# spion.net
KiCad netlist of a schematic drawn in EAGLE
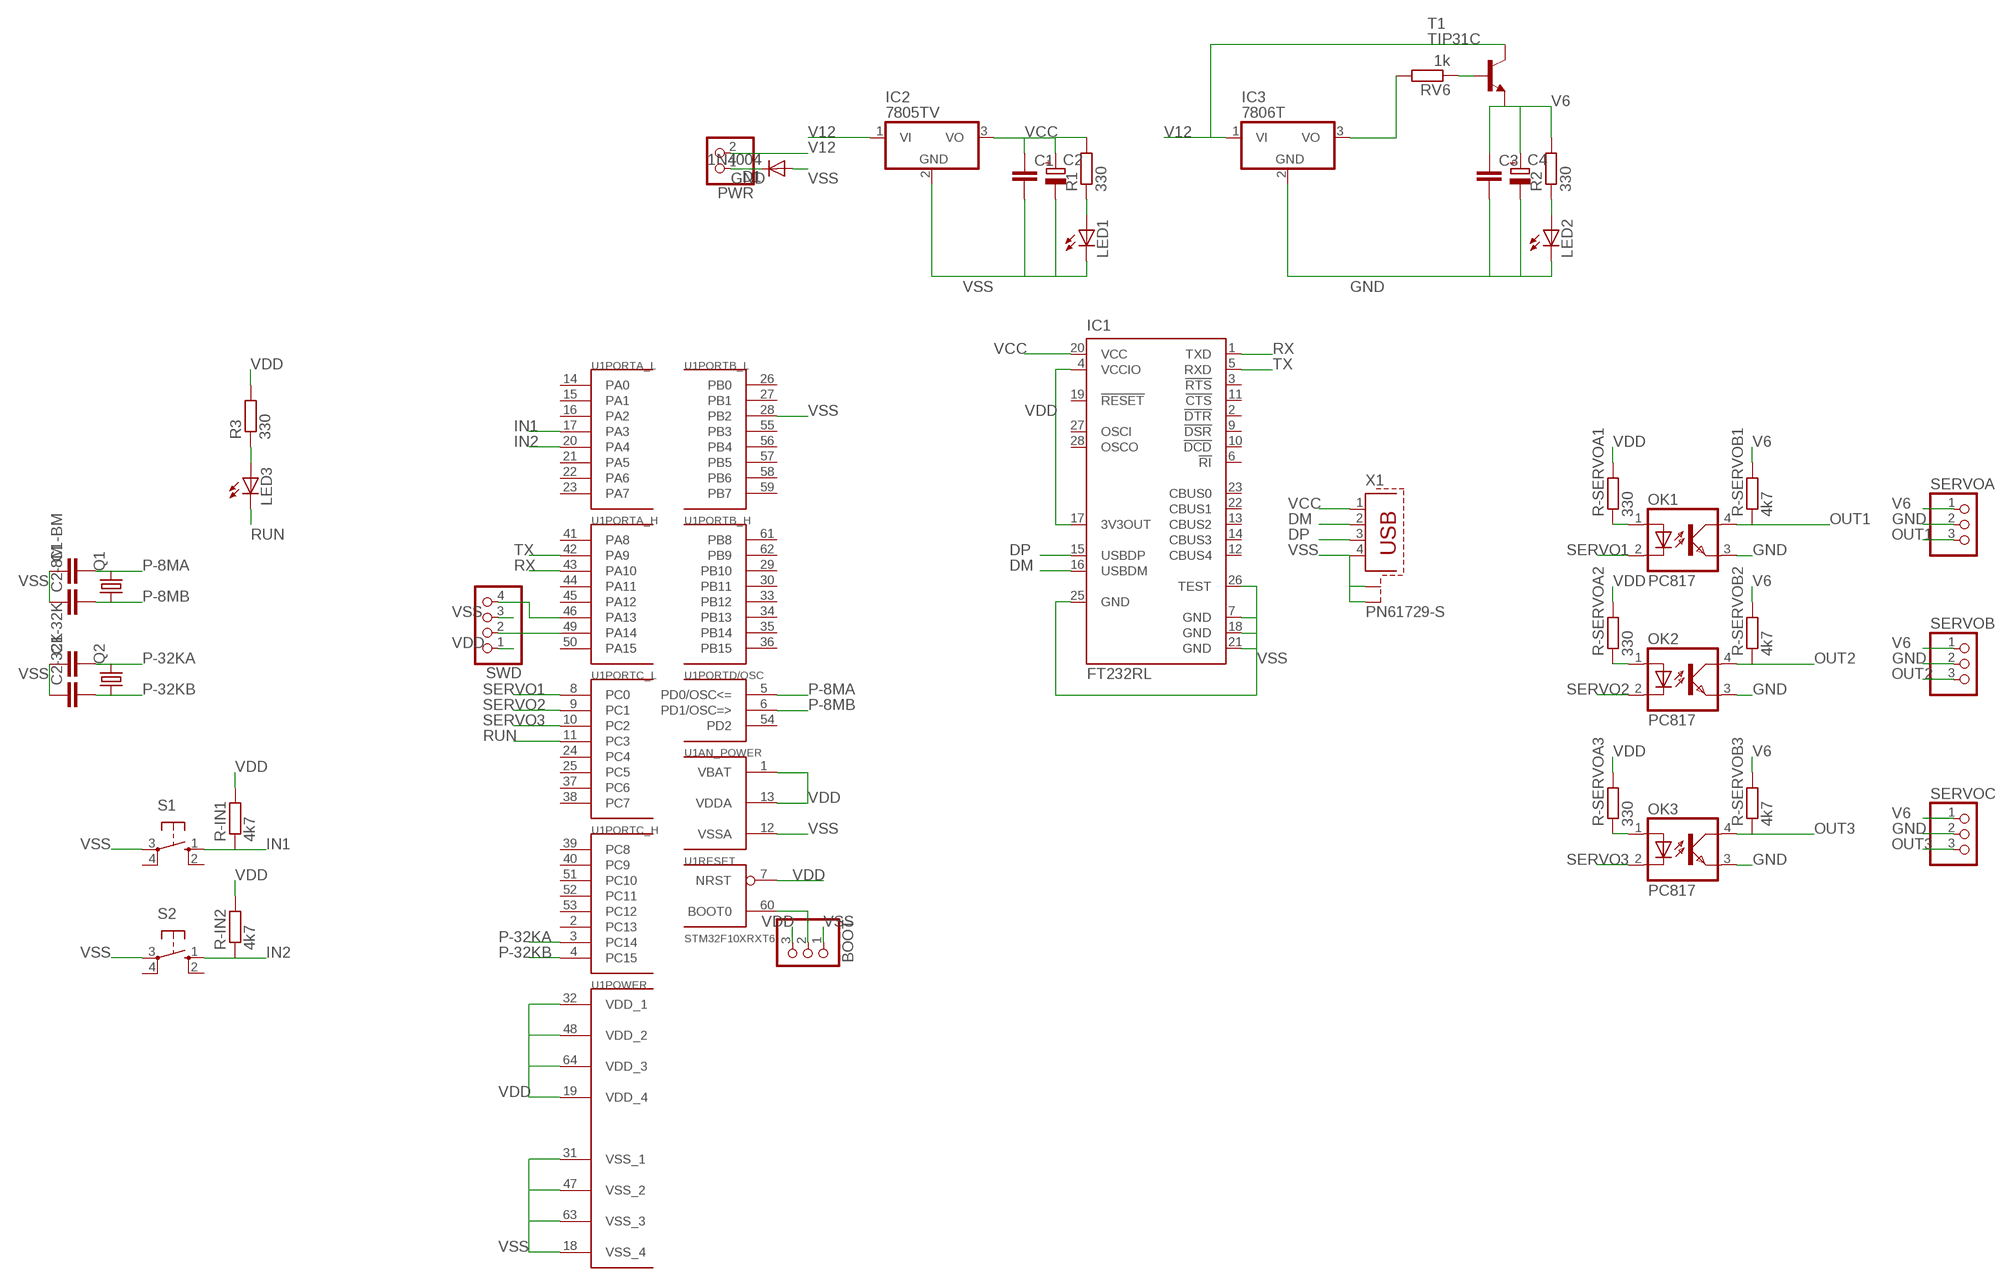
[diagram p0: schematic, sheet 1]

(export (version "E")
  (design (tool "Eeschema 10.0.6"))
  (components
    (comp (ref "BOOT")
      (value "PINHD-1X3")
      (footprint "eagle-import:1X03")
      (libsource (lib "eagle-import") (part "PINHD-1X3"))
    )
    (comp (ref "C1")
      (value "C-EU025-024X044")
      (footprint "eagle-import:C025-024X044")
      (libsource (lib "eagle-import") (part "C-EU025-024X044"))
    )
    (comp (ref "C1-32K")
      (value "C-EU025-024X044")
      (footprint "eagle-import:C025-024X044")
      (libsource (lib "eagle-import") (part "C-EU025-024X044"))
    )
    (comp (ref "C1-BM")
      (value "C-EU025-024X044")
      (footprint "eagle-import:C025-024X044")
      (libsource (lib "eagle-import") (part "C-EU025-024X044"))
    )
    (comp (ref "C2")
      (value "CPOL-EUE2-5")
      (footprint "eagle-import:E2-5")
      (libsource (lib "eagle-import") (part "CPOL-EUE2-5"))
    )
    (comp (ref "C2-8M")
      (value "C-EU025-024X044")
      (footprint "eagle-import:C025-024X044")
      (libsource (lib "eagle-import") (part "C-EU025-024X044"))
    )
    (comp (ref "C2-32K")
      (value "C-EU025-024X044")
      (footprint "eagle-import:C025-024X044")
      (libsource (lib "eagle-import") (part "C-EU025-024X044"))
    )
    (comp (ref "C3")
      (value "C-EU025-024X044")
      (footprint "eagle-import:C025-024X044")
      (libsource (lib "eagle-import") (part "C-EU025-024X044"))
    )
    (comp (ref "C4")
      (value "CPOL-EUE2-5")
      (footprint "eagle-import:E2-5")
      (libsource (lib "eagle-import") (part "CPOL-EUE2-5"))
    )
    (comp (ref "D1")
      (value "1N4004")
      (footprint "eagle-import:DO41-10")
      (libsource (lib "eagle-import") (part "1N4004"))
    )
    (comp (ref "IC1")
      (value "FT232RL")
      (footprint "eagle-import:SSOP28")
      (libsource (lib "eagle-import") (part "FT232RL"))
    )
    (comp (ref "IC2")
      (value "7805TV")
      (footprint "eagle-import:TO220V")
      (libsource (lib "eagle-import") (part "78TV05"))
    )
    (comp (ref "IC3")
      (value "7806T")
      (footprint "eagle-import:TO220H")
      (libsource (lib "eagle-import") (part "78T06"))
    )
    (comp (ref "LED1")
      (value "LED3MM")
      (footprint "eagle-import:LED3MM")
      (libsource (lib "eagle-import") (part "LED3MM"))
    )
    (comp (ref "LED2")
      (value "LED3MM")
      (footprint "eagle-import:LED3MM")
      (libsource (lib "eagle-import") (part "LED3MM"))
    )
    (comp (ref "LED3")
      (value "LED3MM")
      (footprint "eagle-import:LED3MM")
      (libsource (lib "eagle-import") (part "LED3MM"))
    )
    (comp (ref "OK1")
      (value "PC817")
      (footprint "eagle-import:DIL04")
      (fields (field (name "MPN") "PC817X4J000F"))
      (libsource (lib "eagle-import") (part "PC817"))
    )
    (comp (ref "OK2")
      (value "PC817")
      (footprint "eagle-import:DIL04")
      (fields (field (name "MPN") "PC817X4J000F"))
      (libsource (lib "eagle-import") (part "PC817"))
    )
    (comp (ref "OK3")
      (value "PC817")
      (footprint "eagle-import:DIL04")
      (fields (field (name "MPN") "PC817X4J000F"))
      (libsource (lib "eagle-import") (part "PC817"))
    )
    (comp (ref "PWR")
      (value "PINHD-1X2")
      (footprint "eagle-import:1X02")
      (libsource (lib "eagle-import") (part "PINHD-1X2"))
    )
    (comp (ref "Q1")
      (value "CRYSTALHC49S")
      (footprint "eagle-import:HC49_S")
      (libsource (lib "eagle-import") (part "CRYSTALHC49S"))
    )
    (comp (ref "Q2")
      (value "CRYSTALTC26V")
      (footprint "eagle-import:TC26V")
      (libsource (lib "eagle-import") (part "CRYSTALTC26V"))
    )
    (comp (ref "R-IN1")
      (value "4k7")
      (footprint "eagle-import:0204_7")
      (libsource (lib "eagle-import") (part "R-EU_0204/7"))
    )
    (comp (ref "R-IN2")
      (value "4k7")
      (footprint "eagle-import:0204_7")
      (libsource (lib "eagle-import") (part "R-EU_0204/7"))
    )
    (comp (ref "R-SERVOA1")
      (value "330")
      (footprint "eagle-import:0204_7")
      (libsource (lib "eagle-import") (part "R-EU_0204/7"))
    )
    (comp (ref "R-SERVOA2")
      (value "330")
      (footprint "eagle-import:0204_7")
      (libsource (lib "eagle-import") (part "R-EU_0204/7"))
    )
    (comp (ref "R-SERVOA3")
      (value "330")
      (footprint "eagle-import:0204_7")
      (libsource (lib "eagle-import") (part "R-EU_0204/7"))
    )
    (comp (ref "R-SERVOB1")
      (value "4k7")
      (footprint "eagle-import:0204_7")
      (libsource (lib "eagle-import") (part "R-EU_0204/7"))
    )
    (comp (ref "R-SERVOB2")
      (value "4k7")
      (footprint "eagle-import:0204_7")
      (libsource (lib "eagle-import") (part "R-EU_0204/7"))
    )
    (comp (ref "R-SERVOB3")
      (value "4k7")
      (footprint "eagle-import:0204_7")
      (libsource (lib "eagle-import") (part "R-EU_0204/7"))
    )
    (comp (ref "R1")
      (value "330")
      (footprint "eagle-import:0204_7")
      (libsource (lib "eagle-import") (part "R-EU_0204/7"))
    )
    (comp (ref "R2")
      (value "330")
      (footprint "eagle-import:0204_7")
      (libsource (lib "eagle-import") (part "R-EU_0204/7"))
    )
    (comp (ref "R3")
      (value "330")
      (footprint "eagle-import:0204_7")
      (libsource (lib "eagle-import") (part "R-EU_0204/7"))
    )
    (comp (ref "RV6")
      (value "1k")
      (footprint "eagle-import:0204_7")
      (libsource (lib "eagle-import") (part "R-EU_0204/7"))
    )
    (comp (ref "S1")
      (value "10-XX")
      (footprint "eagle-import:B3F-10XX")
      (fields (field (name "MPN") "B3F-1000"))
      (libsource (lib "eagle-import") (part "10-XX"))
    )
    (comp (ref "S2")
      (value "10-XX")
      (footprint "eagle-import:B3F-10XX")
      (fields (field (name "MPN") "B3F-1000"))
      (libsource (lib "eagle-import") (part "10-XX"))
    )
    (comp (ref "SERVOA")
      (value "PINHD-1X3")
      (footprint "eagle-import:1X03")
      (libsource (lib "eagle-import") (part "PINHD-1X3"))
    )
    (comp (ref "SERVOB")
      (value "PINHD-1X3")
      (footprint "eagle-import:1X03")
      (libsource (lib "eagle-import") (part "PINHD-1X3"))
    )
    (comp (ref "SERVOC")
      (value "PINHD-1X3")
      (footprint "eagle-import:1X03")
      (libsource (lib "eagle-import") (part "PINHD-1X3"))
    )
    (comp (ref "SWD")
      (value "PINHD-1X4")
      (footprint "eagle-import:1X04")
      (libsource (lib "eagle-import") (part "PINHD-1X4"))
    )
    (comp (ref "T1")
      (value "TIP31C")
      (footprint "eagle-import:TO220")
      (libsource (lib "eagle-import") (part "TIP31C"))
    )
    (comp (ref "U1")
      (value "STM32F10XRXT6")
      (footprint "eagle-import:TQFP64")
      (libsource (lib "eagle-import") (part "STM32F10XRXT6"))
    )
    (comp (ref "X1")
      (value "PN61729-S")
      (footprint "eagle-import:PN61729-S")
      (libsource (lib "eagle-import") (part "PN61729-S"))
    )
  )
  (nets
    (net (code "1") (name "/DM") (class "Default")
      (node (ref "IC1") (pin "16") (pinfunction "USBDM_16") (pintype "bidirectional"))
      (node (ref "X1") (pin "2") (pinfunction "2_2") (pintype "passive"))
    )
    (net (code "2") (name "/DP") (class "Default")
      (node (ref "IC1") (pin "15") (pinfunction "USBDP_15") (pintype "bidirectional"))
      (node (ref "X1") (pin "3") (pinfunction "3_3") (pintype "passive"))
    )
    (net (code "3") (name "/GND") (class "Default")
      (node (ref "C3") (pin "2") (pinfunction "2_2") (pintype "passive"))
      (node (ref "C4") (pin "-") (pinfunction "-_-") (pintype "passive"))
      (node (ref "D1") (pin "C") (pinfunction "C_C") (pintype "passive"))
      (node (ref "IC3") (pin "2") (pinfunction "GND_2") (pintype "passive"))
      (node (ref "LED2") (pin "K") (pinfunction "C_K") (pintype "passive"))
      (node (ref "OK1") (pin "3") (pinfunction "EMIT_3") (pintype "passive"))
      (node (ref "OK2") (pin "3") (pinfunction "EMIT_3") (pintype "passive"))
      (node (ref "OK3") (pin "3") (pinfunction "EMIT_3") (pintype "passive"))
      (node (ref "PWR") (pin "1") (pinfunction "1_1") (pintype "passive"))
      (node (ref "SERVOA") (pin "2") (pinfunction "2_2") (pintype "passive"))
      (node (ref "SERVOB") (pin "2") (pinfunction "2_2") (pintype "passive"))
      (node (ref "SERVOC") (pin "2") (pinfunction "2_2") (pintype "passive"))
    )
    (net (code "4") (name "/IN1") (class "Default")
      (node (ref "R-IN1") (pin "1") (pinfunction "1_1") (pintype "passive"))
      (node (ref "S1") (pin "1") (pinfunction "S_1") (pintype "passive"))
      (node (ref "U1") (pin "17") (pinfunction "PA3_17") (pintype "bidirectional"))
    )
    (net (code "5") (name "/IN2") (class "Default")
      (node (ref "R-IN2") (pin "1") (pinfunction "1_1") (pintype "passive"))
      (node (ref "S2") (pin "1") (pinfunction "S_1") (pintype "passive"))
      (node (ref "U1") (pin "20") (pinfunction "PA4_20") (pintype "bidirectional"))
    )
    (net (code "6") (name "/OUT1") (class "Default")
      (node (ref "OK1") (pin "4") (pinfunction "COL_4") (pintype "passive"))
      (node (ref "R-SERVOB1") (pin "1") (pinfunction "1_1") (pintype "passive"))
      (node (ref "SERVOA") (pin "3") (pinfunction "3_3") (pintype "passive"))
    )
    (net (code "7") (name "/OUT2") (class "Default")
      (node (ref "OK2") (pin "4") (pinfunction "COL_4") (pintype "passive"))
      (node (ref "R-SERVOB2") (pin "1") (pinfunction "1_1") (pintype "passive"))
      (node (ref "SERVOB") (pin "3") (pinfunction "3_3") (pintype "passive"))
    )
    (net (code "8") (name "/OUT3") (class "Default")
      (node (ref "OK3") (pin "4") (pinfunction "COL_4") (pintype "passive"))
      (node (ref "R-SERVOB3") (pin "1") (pinfunction "1_1") (pintype "passive"))
      (node (ref "SERVOC") (pin "3") (pinfunction "3_3") (pintype "passive"))
    )
    (net (code "9") (name "/P-8MA") (class "Default")
      (node (ref "C1-BM") (pin "2") (pinfunction "2_2") (pintype "passive"))
      (node (ref "Q1") (pin "2") (pinfunction "2_2") (pintype "passive"))
      (node (ref "U1") (pin "5") (pinfunction "PD0/OSC<=_5") (pintype "bidirectional"))
    )
    (net (code "10") (name "/P-8MB") (class "Default")
      (node (ref "C2-8M") (pin "2") (pinfunction "2_2") (pintype "passive"))
      (node (ref "Q1") (pin "1") (pinfunction "1_1") (pintype "passive"))
      (node (ref "U1") (pin "6") (pinfunction "PD1/OSC=>_6") (pintype "bidirectional"))
    )
    (net (code "11") (name "/P-32KA") (class "Default")
      (node (ref "C1-32K") (pin "2") (pinfunction "2_2") (pintype "passive"))
      (node (ref "Q2") (pin "2") (pinfunction "2_2") (pintype "passive"))
      (node (ref "U1") (pin "3") (pinfunction "PC14_3") (pintype "bidirectional"))
    )
    (net (code "12") (name "/P-32KB") (class "Default")
      (node (ref "C2-32K") (pin "2") (pinfunction "2_2") (pintype "passive"))
      (node (ref "Q2") (pin "1") (pinfunction "1_1") (pintype "passive"))
      (node (ref "U1") (pin "4") (pinfunction "PC15_4") (pintype "bidirectional"))
    )
    (net (code "13") (name "/RUN") (class "Default")
      (node (ref "LED3") (pin "K") (pinfunction "C_K") (pintype "passive"))
      (node (ref "U1") (pin "11") (pinfunction "PC3_11") (pintype "bidirectional"))
    )
    (net (code "14") (name "/RX") (class "Default")
      (node (ref "IC1") (pin "1") (pinfunction "TXD_1") (pintype "output"))
      (node (ref "U1") (pin "43") (pinfunction "PA10_43") (pintype "bidirectional"))
    )
    (net (code "15") (name "/SERVO1") (class "Default")
      (node (ref "OK1") (pin "2") (pinfunction "C_2") (pintype "passive"))
      (node (ref "U1") (pin "8") (pinfunction "PC0_8") (pintype "bidirectional"))
    )
    (net (code "16") (name "/SERVO2") (class "Default")
      (node (ref "OK2") (pin "2") (pinfunction "C_2") (pintype "passive"))
      (node (ref "U1") (pin "9") (pinfunction "PC1_9") (pintype "bidirectional"))
    )
    (net (code "17") (name "/SERVO3") (class "Default")
      (node (ref "OK3") (pin "2") (pinfunction "C_2") (pintype "passive"))
      (node (ref "U1") (pin "10") (pinfunction "PC2_10") (pintype "bidirectional"))
    )
    (net (code "18") (name "/TX") (class "Default")
      (node (ref "IC1") (pin "5") (pinfunction "RXD_5") (pintype "input"))
      (node (ref "U1") (pin "42") (pinfunction "PA9_42") (pintype "bidirectional"))
    )
    (net (code "19") (name "/V6") (class "Default")
      (node (ref "C3") (pin "1") (pinfunction "1_1") (pintype "passive"))
      (node (ref "C4") (pin "+") (pinfunction "+_+") (pintype "passive"))
      (node (ref "R-SERVOB1") (pin "2") (pinfunction "2_2") (pintype "passive"))
      (node (ref "R-SERVOB2") (pin "2") (pinfunction "2_2") (pintype "passive"))
      (node (ref "R-SERVOB3") (pin "2") (pinfunction "2_2") (pintype "passive"))
      (node (ref "R2") (pin "2") (pinfunction "2_2") (pintype "passive"))
      (node (ref "SERVOA") (pin "1") (pinfunction "1_1") (pintype "passive"))
      (node (ref "SERVOB") (pin "1") (pinfunction "1_1") (pintype "passive"))
      (node (ref "SERVOC") (pin "1") (pinfunction "1_1") (pintype "passive"))
      (node (ref "T1") (pin "3") (pinfunction "E_3") (pintype "passive"))
    )
    (net (code "20") (name "/V12") (class "Default")
      (node (ref "IC2") (pin "1") (pinfunction "VI_1") (pintype "input"))
      (node (ref "IC3") (pin "1") (pinfunction "VI_1") (pintype "input"))
      (node (ref "PWR") (pin "2") (pinfunction "2_2") (pintype "passive"))
      (node (ref "T1") (pin "2") (pinfunction "C_2") (pintype "passive"))
    )
    (net (code "21") (name "/VCC") (class "Default")
      (node (ref "C1") (pin "1") (pinfunction "1_1") (pintype "passive"))
      (node (ref "C2") (pin "+") (pinfunction "+_+") (pintype "passive"))
      (node (ref "IC1") (pin "20") (pinfunction "VCC_20") (pintype "power_in"))
      (node (ref "IC2") (pin "3") (pinfunction "VO_3") (pintype "passive"))
      (node (ref "R1") (pin "2") (pinfunction "2_2") (pintype "passive"))
      (node (ref "X1") (pin "1") (pinfunction "1_1") (pintype "passive"))
    )
    (net (code "22") (name "/VDD") (class "Default")
      (node (ref "BOOT") (pin "3") (pinfunction "3_3") (pintype "passive"))
      (node (ref "IC1") (pin "17") (pinfunction "3V3OUT_17") (pintype "output"))
      (node (ref "IC1") (pin "4") (pinfunction "VCCIO_4") (pintype "power_in"))
      (node (ref "R-IN1") (pin "2") (pinfunction "2_2") (pintype "passive"))
      (node (ref "R-IN2") (pin "2") (pinfunction "2_2") (pintype "passive"))
      (node (ref "R-SERVOA1") (pin "2") (pinfunction "2_2") (pintype "passive"))
      (node (ref "R-SERVOA2") (pin "2") (pinfunction "2_2") (pintype "passive"))
      (node (ref "R-SERVOA3") (pin "2") (pinfunction "2_2") (pintype "passive"))
      (node (ref "R3") (pin "2") (pinfunction "2_2") (pintype "passive"))
      (node (ref "SWD") (pin "1") (pinfunction "1_1") (pintype "passive"))
      (node (ref "U1") (pin "1") (pinfunction "VBAT_1") (pintype "power_in"))
      (node (ref "U1") (pin "13") (pinfunction "VDDA_13") (pintype "power_in"))
      (node (ref "U1") (pin "19") (pinfunction "VDD_4_19") (pintype "power_in"))
      (node (ref "U1") (pin "32") (pinfunction "VDD_1_32") (pintype "power_in"))
      (node (ref "U1") (pin "48") (pinfunction "VDD_2_48") (pintype "power_in"))
      (node (ref "U1") (pin "64") (pinfunction "VDD_3_64") (pintype "power_in"))
      (node (ref "U1") (pin "7") (pinfunction "NRST_7") (pintype "input"))
    )
    (net (code "23") (name "/VSS") (class "Default")
      (node (ref "BOOT") (pin "1") (pinfunction "1_1") (pintype "passive"))
      (node (ref "C1") (pin "2") (pinfunction "2_2") (pintype "passive"))
      (node (ref "C1-32K") (pin "1") (pinfunction "1_1") (pintype "passive"))
      (node (ref "C1-BM") (pin "1") (pinfunction "1_1") (pintype "passive"))
      (node (ref "C2") (pin "-") (pinfunction "-_-") (pintype "passive"))
      (node (ref "C2-32K") (pin "1") (pinfunction "1_1") (pintype "passive"))
      (node (ref "C2-8M") (pin "1") (pinfunction "1_1") (pintype "passive"))
      (node (ref "D1") (pin "A") (pinfunction "A_A") (pintype "passive"))
      (node (ref "IC1") (pin "18") (pinfunction "GND_18") (pintype "power_in"))
      (node (ref "IC1") (pin "21") (pinfunction "GND_21") (pintype "power_in"))
      (node (ref "IC1") (pin "25") (pinfunction "GND_25") (pintype "power_in"))
      (node (ref "IC1") (pin "26") (pinfunction "TEST_26") (pintype "input"))
      (node (ref "IC1") (pin "7") (pinfunction "GND_7") (pintype "power_in"))
      (node (ref "IC2") (pin "2") (pinfunction "GND_2") (pintype "passive"))
      (node (ref "LED1") (pin "K") (pinfunction "C_K") (pintype "passive"))
      (node (ref "S1") (pin "3") (pinfunction "P_3") (pintype "passive"))
      (node (ref "S2") (pin "3") (pinfunction "P_3") (pintype "passive"))
      (node (ref "SWD") (pin "3") (pinfunction "3_3") (pintype "passive"))
      (node (ref "U1") (pin "12") (pinfunction "VSSA_12") (pintype "power_in"))
      (node (ref "U1") (pin "18") (pinfunction "VSS_4_18") (pintype "power_in"))
      (node (ref "U1") (pin "28") (pinfunction "PB2_28") (pintype "bidirectional"))
      (node (ref "U1") (pin "31") (pinfunction "VSS_1_31") (pintype "power_in"))
      (node (ref "U1") (pin "47") (pinfunction "VSS_2_47") (pintype "power_in"))
      (node (ref "U1") (pin "63") (pinfunction "VSS_3_63") (pintype "power_in"))
      (node (ref "X1") (pin "4") (pinfunction "4_4") (pintype "passive"))
      (node (ref "X1") (pin "S1") (pinfunction "S1_S1") (pintype "passive"))
      (node (ref "X1") (pin "S2") (pinfunction "S2_S2") (pintype "passive"))
    )
    (net (code "24") (name "Net-(IC3-VO)") (class "Default")
      (node (ref "IC3") (pin "3") (pinfunction "VO_3") (pintype "passive"))
      (node (ref "RV6") (pin "2") (pinfunction "2_2") (pintype "passive"))
    )
    (net (code "25") (name "Net-(LED1-PadA)") (class "Default")
      (node (ref "LED1") (pin "A") (pinfunction "A_A") (pintype "passive"))
      (node (ref "R1") (pin "1") (pinfunction "1_1") (pintype "passive"))
    )
    (net (code "26") (name "Net-(LED2-PadA)") (class "Default")
      (node (ref "LED2") (pin "A") (pinfunction "A_A") (pintype "passive"))
      (node (ref "R2") (pin "1") (pinfunction "1_1") (pintype "passive"))
    )
    (net (code "27") (name "Net-(LED3-PadA)") (class "Default")
      (node (ref "LED3") (pin "A") (pinfunction "A_A") (pintype "passive"))
      (node (ref "R3") (pin "1") (pinfunction "1_1") (pintype "passive"))
    )
    (net (code "28") (name "Net-(OK1-A)") (class "Default")
      (node (ref "OK1") (pin "1") (pinfunction "A_1") (pintype "passive"))
      (node (ref "R-SERVOA1") (pin "1") (pinfunction "1_1") (pintype "passive"))
    )
    (net (code "29") (name "Net-(OK2-A)") (class "Default")
      (node (ref "OK2") (pin "1") (pinfunction "A_1") (pintype "passive"))
      (node (ref "R-SERVOA2") (pin "1") (pinfunction "1_1") (pintype "passive"))
    )
    (net (code "30") (name "Net-(OK3-A)") (class "Default")
      (node (ref "OK3") (pin "1") (pinfunction "A_1") (pintype "passive"))
      (node (ref "R-SERVOA3") (pin "1") (pinfunction "1_1") (pintype "passive"))
    )
    (net (code "31") (name "Net-(T1-B)") (class "Default")
      (node (ref "RV6") (pin "1") (pinfunction "1_1") (pintype "passive"))
      (node (ref "T1") (pin "1") (pinfunction "B_1") (pintype "passive"))
    )
    (net (code "32") (name "Net-(U1B-PA13)") (class "Default")
      (node (ref "SWD") (pin "4") (pinfunction "4_4") (pintype "passive"))
      (node (ref "U1") (pin "46") (pinfunction "PA13_46") (pintype "bidirectional"))
    )
    (net (code "33") (name "Net-(U1B-PA14)") (class "Default")
      (node (ref "SWD") (pin "2") (pinfunction "2_2") (pintype "passive"))
      (node (ref "U1") (pin "49") (pinfunction "PA14_49") (pintype "bidirectional"))
    )
    (net (code "34") (name "Net-(U1J-BOOT0)") (class "Default")
      (node (ref "BOOT") (pin "2") (pinfunction "2_2") (pintype "passive"))
      (node (ref "U1") (pin "60") (pinfunction "BOOT0_60") (pintype "input"))
    )
    (net (code "35") (name "unconnected-(IC1-CBUS0-Pad23)") (class "Default")
      (node (ref "IC1") (pin "23") (pinfunction "CBUS0_23") (pintype "bidirectional"))
    )
    (net (code "36") (name "unconnected-(IC1-CBUS1-Pad22)") (class "Default")
      (node (ref "IC1") (pin "22") (pinfunction "CBUS1_22") (pintype "bidirectional"))
    )
    (net (code "37") (name "unconnected-(IC1-CBUS2-Pad13)") (class "Default")
      (node (ref "IC1") (pin "13") (pinfunction "CBUS2_13") (pintype "bidirectional"))
    )
    (net (code "38") (name "unconnected-(IC1-CBUS3-Pad14)") (class "Default")
      (node (ref "IC1") (pin "14") (pinfunction "CBUS3_14") (pintype "bidirectional"))
    )
    (net (code "39") (name "unconnected-(IC1-CBUS4-Pad12)") (class "Default")
      (node (ref "IC1") (pin "12") (pinfunction "CBUS4_12") (pintype "bidirectional"))
    )
    (net (code "40") (name "unconnected-(IC1-OSCI-Pad27)") (class "Default")
      (node (ref "IC1") (pin "27") (pinfunction "OSCI_27") (pintype "input"))
    )
    (net (code "41") (name "unconnected-(IC1-OSCO-Pad28)") (class "Default")
      (node (ref "IC1") (pin "28") (pinfunction "OSCO_28") (pintype "output"))
    )
    (net (code "42") (name "unconnected-(IC1-~{CTS}-Pad11)") (class "Default")
      (node (ref "IC1") (pin "11") (pinfunction "~{CTS}_11") (pintype "input"))
    )
    (net (code "43") (name "unconnected-(IC1-~{DCD}-Pad10)") (class "Default")
      (node (ref "IC1") (pin "10") (pinfunction "~{DCD}_10") (pintype "input"))
    )
    (net (code "44") (name "unconnected-(IC1-~{DSR}-Pad9)") (class "Default")
      (node (ref "IC1") (pin "9") (pinfunction "~{DSR}_9") (pintype "input"))
    )
    (net (code "45") (name "unconnected-(IC1-~{DTR}-Pad2)") (class "Default")
      (node (ref "IC1") (pin "2") (pinfunction "~{DTR}_2") (pintype "output"))
    )
    (net (code "46") (name "unconnected-(IC1-~{RESET}-Pad19)") (class "Default")
      (node (ref "IC1") (pin "19") (pinfunction "~{RESET}_19") (pintype "input"))
    )
    (net (code "47") (name "unconnected-(IC1-~{RI}-Pad6)") (class "Default")
      (node (ref "IC1") (pin "6") (pinfunction "~{RI}_6") (pintype "input"))
    )
    (net (code "48") (name "unconnected-(IC1-~{RTS}-Pad3)") (class "Default")
      (node (ref "IC1") (pin "3") (pinfunction "~{RTS}_3") (pintype "output"))
    )
    (net (code "49") (name "unconnected-(S1-P1-Pad4)") (class "Default")
      (node (ref "S1") (pin "4") (pinfunction "P1_4") (pintype "passive"))
    )
    (net (code "50") (name "unconnected-(S1-S1-Pad2)") (class "Default")
      (node (ref "S1") (pin "2") (pinfunction "S1_2") (pintype "passive"))
    )
    (net (code "51") (name "unconnected-(S2-P1-Pad4)") (class "Default")
      (node (ref "S2") (pin "4") (pinfunction "P1_4") (pintype "passive"))
    )
    (net (code "52") (name "unconnected-(S2-S1-Pad2)") (class "Default")
      (node (ref "S2") (pin "2") (pinfunction "S1_2") (pintype "passive"))
    )
    (net (code "53") (name "unconnected-(U1B-PA8-Pad41)") (class "Default")
      (node (ref "U1") (pin "41") (pinfunction "PA8_41") (pintype "bidirectional"))
    )
    (net (code "54") (name "unconnected-(U1B-PA11-Pad44)") (class "Default")
      (node (ref "U1") (pin "44") (pinfunction "PA11_44") (pintype "bidirectional"))
    )
    (net (code "55") (name "unconnected-(U1B-PA12-Pad45)") (class "Default")
      (node (ref "U1") (pin "45") (pinfunction "PA12_45") (pintype "bidirectional"))
    )
    (net (code "56") (name "unconnected-(U1B-PA15-Pad50)") (class "Default")
      (node (ref "U1") (pin "50") (pinfunction "PA15_50") (pintype "bidirectional"))
    )
    (net (code "57") (name "unconnected-(U1C-PA0-Pad14)") (class "Default")
      (node (ref "U1") (pin "14") (pinfunction "PA0_14") (pintype "bidirectional"))
    )
    (net (code "58") (name "unconnected-(U1C-PA1-Pad15)") (class "Default")
      (node (ref "U1") (pin "15") (pinfunction "PA1_15") (pintype "bidirectional"))
    )
    (net (code "59") (name "unconnected-(U1C-PA2-Pad16)") (class "Default")
      (node (ref "U1") (pin "16") (pinfunction "PA2_16") (pintype "bidirectional"))
    )
    (net (code "60") (name "unconnected-(U1C-PA5-Pad21)") (class "Default")
      (node (ref "U1") (pin "21") (pinfunction "PA5_21") (pintype "bidirectional"))
    )
    (net (code "61") (name "unconnected-(U1C-PA6-Pad22)") (class "Default")
      (node (ref "U1") (pin "22") (pinfunction "PA6_22") (pintype "bidirectional"))
    )
    (net (code "62") (name "unconnected-(U1C-PA7-Pad23)") (class "Default")
      (node (ref "U1") (pin "23") (pinfunction "PA7_23") (pintype "bidirectional"))
    )
    (net (code "63") (name "unconnected-(U1D-PB8-Pad61)") (class "Default")
      (node (ref "U1") (pin "61") (pinfunction "PB8_61") (pintype "bidirectional"))
    )
    (net (code "64") (name "unconnected-(U1D-PB9-Pad62)") (class "Default")
      (node (ref "U1") (pin "62") (pinfunction "PB9_62") (pintype "bidirectional"))
    )
    (net (code "65") (name "unconnected-(U1D-PB10-Pad29)") (class "Default")
      (node (ref "U1") (pin "29") (pinfunction "PB10_29") (pintype "bidirectional"))
    )
    (net (code "66") (name "unconnected-(U1D-PB11-Pad30)") (class "Default")
      (node (ref "U1") (pin "30") (pinfunction "PB11_30") (pintype "bidirectional"))
    )
    (net (code "67") (name "unconnected-(U1D-PB12-Pad33)") (class "Default")
      (node (ref "U1") (pin "33") (pinfunction "PB12_33") (pintype "bidirectional"))
    )
    (net (code "68") (name "unconnected-(U1D-PB13-Pad34)") (class "Default")
      (node (ref "U1") (pin "34") (pinfunction "PB13_34") (pintype "bidirectional"))
    )
    (net (code "69") (name "unconnected-(U1D-PB14-Pad35)") (class "Default")
      (node (ref "U1") (pin "35") (pinfunction "PB14_35") (pintype "bidirectional"))
    )
    (net (code "70") (name "unconnected-(U1D-PB15-Pad36)") (class "Default")
      (node (ref "U1") (pin "36") (pinfunction "PB15_36") (pintype "bidirectional"))
    )
    (net (code "71") (name "unconnected-(U1E-PB0-Pad26)") (class "Default")
      (node (ref "U1") (pin "26") (pinfunction "PB0_26") (pintype "bidirectional"))
    )
    (net (code "72") (name "unconnected-(U1E-PB1-Pad27)") (class "Default")
      (node (ref "U1") (pin "27") (pinfunction "PB1_27") (pintype "bidirectional"))
    )
    (net (code "73") (name "unconnected-(U1E-PB3-Pad55)") (class "Default")
      (node (ref "U1") (pin "55") (pinfunction "PB3_55") (pintype "bidirectional"))
    )
    (net (code "74") (name "unconnected-(U1E-PB4-Pad56)") (class "Default")
      (node (ref "U1") (pin "56") (pinfunction "PB4_56") (pintype "bidirectional"))
    )
    (net (code "75") (name "unconnected-(U1E-PB5-Pad57)") (class "Default")
      (node (ref "U1") (pin "57") (pinfunction "PB5_57") (pintype "bidirectional"))
    )
    (net (code "76") (name "unconnected-(U1E-PB6-Pad58)") (class "Default")
      (node (ref "U1") (pin "58") (pinfunction "PB6_58") (pintype "bidirectional"))
    )
    (net (code "77") (name "unconnected-(U1E-PB7-Pad59)") (class "Default")
      (node (ref "U1") (pin "59") (pinfunction "PB7_59") (pintype "bidirectional"))
    )
    (net (code "78") (name "unconnected-(U1F-PC8-Pad39)") (class "Default")
      (node (ref "U1") (pin "39") (pinfunction "PC8_39") (pintype "bidirectional"))
    )
    (net (code "79") (name "unconnected-(U1F-PC9-Pad40)") (class "Default")
      (node (ref "U1") (pin "40") (pinfunction "PC9_40") (pintype "bidirectional"))
    )
    (net (code "80") (name "unconnected-(U1F-PC10-Pad51)") (class "Default")
      (node (ref "U1") (pin "51") (pinfunction "PC10_51") (pintype "bidirectional"))
    )
    (net (code "81") (name "unconnected-(U1F-PC11-Pad52)") (class "Default")
      (node (ref "U1") (pin "52") (pinfunction "PC11_52") (pintype "bidirectional"))
    )
    (net (code "82") (name "unconnected-(U1F-PC12-Pad53)") (class "Default")
      (node (ref "U1") (pin "53") (pinfunction "PC12_53") (pintype "bidirectional"))
    )
    (net (code "83") (name "unconnected-(U1F-PC13-Pad2)") (class "Default")
      (node (ref "U1") (pin "2") (pinfunction "PC13_2") (pintype "bidirectional"))
    )
    (net (code "84") (name "unconnected-(U1G-PC4-Pad24)") (class "Default")
      (node (ref "U1") (pin "24") (pinfunction "PC4_24") (pintype "bidirectional"))
    )
    (net (code "85") (name "unconnected-(U1G-PC5-Pad25)") (class "Default")
      (node (ref "U1") (pin "25") (pinfunction "PC5_25") (pintype "bidirectional"))
    )
    (net (code "86") (name "unconnected-(U1G-PC6-Pad37)") (class "Default")
      (node (ref "U1") (pin "37") (pinfunction "PC6_37") (pintype "bidirectional"))
    )
    (net (code "87") (name "unconnected-(U1G-PC7-Pad38)") (class "Default")
      (node (ref "U1") (pin "38") (pinfunction "PC7_38") (pintype "bidirectional"))
    )
    (net (code "88") (name "unconnected-(U1H-PD2-Pad54)") (class "Default")
      (node (ref "U1") (pin "54") (pinfunction "PD2_54") (pintype "bidirectional"))
    )
  )
)
